# Regulators.net
KiCad netlist of a schematic drawn in Altium Designer
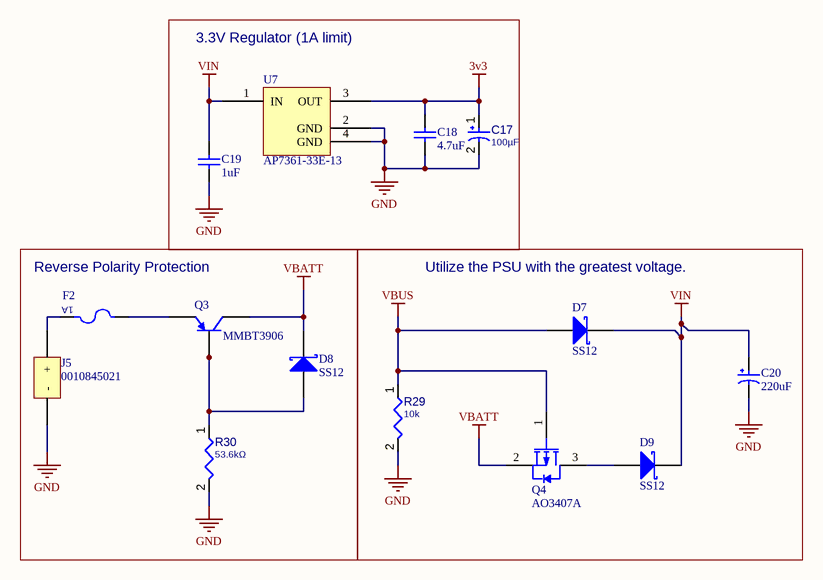
[diagram p0: Regulators.SchDoc]

(export (version "E")
  (design (tool "Eeschema 10.0.6"))
  (components
    (comp (ref "C17")
      (value "100µF")
      (footprint "KEMT-T491-D_M")
      (fields
        (field (name "TOLERANCE") "10%")
        (field (name "MANUFACTURER") "Kemet")
        (field (name "Comment") "T491D107K010AT")
      )
      (libsource (lib "RIT Launch Initiative") (part "CAP-P-2"))
    )
    (comp (ref "C18")
      (value "GRM155R60J475ME87D")
      (footprint "Capacitor_0402")
      (description "6.3V 4.7uF X5R ±20% 0402 Multilayer Ceramic Capacitors MLCC - SMD/SMT ROHS")
      (fields (field (name "CAPACITANCE") "4.7uF") (field (name "TOLERANCE") "20%"))
      (libsource (lib "RIT Launch Initiative") (part "CAPACITOR"))
    )
    (comp (ref "C19")
      (value "GRM155R61E105KA12D")
      (footprint "Capacitor_0402")
      (description "Chip Capacitor 1uF - 0402 25 V ±10% Tolerance X5R Multilayer Ceramic Chip Capacitor")
      (fields (field (name "CAPACITANCE") "1uF") (field (name "TOLERANCE") "10%"))
      (libsource (lib "RIT Launch Initiative") (part "CAPACITOR"))
    )
    (comp (ref "C20")
      (value "T491D227K010AT")
      (footprint "CASE-D_7343")
      (description "Cap Tant Solid 220uF 10V D CASE 10% (7.3 X 4.3 X 2.8mm) SMD 7343-31 0.5 Ohm 125 C T/R")
      (fields (field (name "CAPACITANCE") "220uF") (field (name "TOLERANCE") "10%"))
      (libsource (lib "RIT Launch Initiative") (part "CAPACITOR POLARIZED"))
    )
    (comp (ref "D7")
      (value "SS12")
      (footprint "FAIR-DO-214AC-2_V")
      (description "Schottky Rectifier, 20 V, 1 A, -65 to 125 degC, 2-Pin DO-214AC, RoHS, Tape and Reel")
      (fields (field (name "MANUFACTURER") "Fairchild"))
      (libsource (lib "RIT Launch Initiative") (part "DSKY-AK-2"))
    )
    (comp (ref "D8")
      (value "SS12")
      (footprint "FAIR-DO-214AC-2_V")
      (description "Schottky Rectifier, 20 V, 1 A, -65 to 125 degC, 2-Pin DO-214AC, RoHS, Tape and Reel")
      (fields (field (name "MANUFACTURER") "Fairchild"))
      (libsource (lib "RIT Launch Initiative") (part "DSKY-AK-2"))
    )
    (comp (ref "D9")
      (value "SS12")
      (footprint "FAIR-DO-214AC-2_V")
      (description "Schottky Rectifier, 20 V, 1 A, -65 to 125 degC, 2-Pin DO-214AC, RoHS, Tape and Reel")
      (fields (field (name "MANUFACTURER") "Fairchild"))
      (libsource (lib "RIT Launch Initiative") (part "DSKY-AK-2"))
    )
    (comp (ref "F2")
      (value "0466001.NRHF")
      (footprint "FP-0466-MFG")
      (description "Fuse Chip Very Fast Acting 1A 63V SMD Solder Pad 1206 T/R CSA")
      (libsource (lib "RIT Launch Initiative") (part "FUSE"))
    )
    (comp (ref "J5")
      (value "0010845021")
      (footprint "0010845021-Footprint-1")
      (description "Header Connector, pcb Mount, plug, 2 Contacts, skt, 0.25 Pitch, pc Tail Terminal, polarized Lck")
      (libsource (lib "RIT Launch Initiative") (part "0010845021"))
    )
    (comp (ref "Q3")
      (value "MMBT3906")
      (footprint "FAIR-SOT23-3_V")
      (description "PNP General-Purpose Amplifier, 40 V, 0.2 A, -55 to 150 degC, 3-Pin SOT23, RoHS, Tape and Reel")
      (fields (field (name "MANUFACTURER") "Fairchild") (field (name "POWER") "350mW"))
      (libsource (lib "RIT Launch Initiative") (part "BJT-PNP-BEC-3"))
    )
    (comp (ref "Q4")
      (value "AO3407A")
      (footprint "AO3407A")
      (description "P-Channel 30 V 4.3A (Ta) 1.4W (Ta) Surface Mount SOT-23-3")
      (libsource (lib "Schlib1") (part "AO3407A"))
    )
    (comp (ref "R29")
      (value "10k")
      (footprint "RESC0402(1005)_L")
      (description "Chip Resistor, 10 kOhms, +/-1 %, 63 mW, -55 to 125 degC, 0402")
      (fields (field (name "POWER") "63mW") (field (name "TOLERANCE") "1%"))
      (libsource (lib "RIT Launch Initiative") (part "RES-2"))
    )
    (comp (ref "R30")
      (value "53.6kΩ")
      (footprint "RESC0402(1005)_L")
      (description "53K6 0.063W 1% 0402 (1005 Metric)  SMD")
      (fields (field (name "POWER") "63mW") (field (name "TOLERANCE") "1%"))
      (libsource (lib "RIT Launch Initiative") (part "53D6KR2F"))
    )
    (comp (ref "U7")
      (value "AP7361-33E-13")
      (footprint "AP7361-33E-13-Footprint-1")
      (description "AP7361 Series 3.3 V 1 A Low SMT Dropout Fixed-Mode Regulator - SOT-223")
      (libsource (lib "RIT Launch Initiative") (part "AP7361-33E-13-Symbol-1"))
    )
  )
  (nets
    (net (code "1") (name "3v3") (class "Default")
      (node (ref "C17") (pin "1") (pinfunction "1_1") (pintype "passive"))
      (node (ref "C18") (pin "2") (pinfunction "2_2") (pintype "passive"))
      (node (ref "U7") (pin "3") (pinfunction "OUT_3") (pintype "passive"))
    )
    (net (code "2") (name "GND") (class "Default")
      (node (ref "C17") (pin "2") (pinfunction "2_2") (pintype "passive"))
      (node (ref "C18") (pin "1") (pinfunction "1_1") (pintype "passive"))
      (node (ref "C19") (pin "1") (pinfunction "1_1") (pintype "passive"))
      (node (ref "C20") (pin "2") (pinfunction "2_2") (pintype "passive"))
      (node (ref "J5") (pin "2") (pinfunction "-_2") (pintype "passive"))
      (node (ref "R29") (pin "2") (pinfunction "2_2") (pintype "passive"))
      (node (ref "R30") (pin "2") (pinfunction "2_2") (pintype "passive"))
      (node (ref "U7") (pin "2") (pinfunction "GND_2") (pintype "passive"))
      (node (ref "U7") (pin "4") (pinfunction "GND_4") (pintype "passive"))
    )
    (net (code "3") (name "Net-(D8-A)") (class "Default")
      (node (ref "D8") (pin "1") (pinfunction "A_1") (pintype "passive"))
      (node (ref "Q3") (pin "1") (pinfunction "B_1") (pintype "passive"))
      (node (ref "R30") (pin "1") (pinfunction "1_1") (pintype "passive"))
    )
    (net (code "4") (name "Net-(D9-A)") (class "Default")
      (node (ref "D9") (pin "1") (pinfunction "A_1") (pintype "passive"))
      (node (ref "Q4") (pin "3") (pinfunction "DRAIN_3") (pintype "passive"))
    )
    (net (code "5") (name "Net-(J5-+)") (class "Default")
      (node (ref "F2") (pin "2") (pinfunction "2_2") (pintype "passive"))
      (node (ref "J5") (pin "1") (pinfunction "+_1") (pintype "passive"))
    )
    (net (code "6") (name "Net-(Q3-E)") (class "Default")
      (node (ref "F2") (pin "1") (pinfunction "1_1") (pintype "passive"))
      (node (ref "Q3") (pin "2") (pinfunction "E_2") (pintype "passive"))
    )
    (net (code "7") (name "VBATT") (class "Default")
      (node (ref "D8") (pin "2") (pinfunction "K_2") (pintype "passive"))
      (node (ref "Q3") (pin "3") (pinfunction "C_3") (pintype "passive"))
      (node (ref "Q4") (pin "2") (pinfunction "SOURCE_2") (pintype "passive"))
    )
    (net (code "8") (name "VBUS") (class "Default")
      (node (ref "D7") (pin "1") (pinfunction "A_1") (pintype "passive"))
      (node (ref "Q4") (pin "1") (pinfunction "GATE_1") (pintype "passive"))
      (node (ref "R29") (pin "1") (pinfunction "1_1") (pintype "passive"))
    )
    (net (code "9") (name "VIN") (class "Default")
      (node (ref "C19") (pin "2") (pinfunction "2_2") (pintype "passive"))
      (node (ref "C20") (pin "1") (pinfunction "1_1") (pintype "passive"))
      (node (ref "D7") (pin "2") (pinfunction "K_2") (pintype "passive"))
      (node (ref "D9") (pin "2") (pinfunction "K_2") (pintype "passive"))
      (node (ref "U7") (pin "1") (pinfunction "IN_1") (pintype "passive"))
    )
  )
)
